# Host.net
KiCad netlist of a schematic drawn in Altium Designer
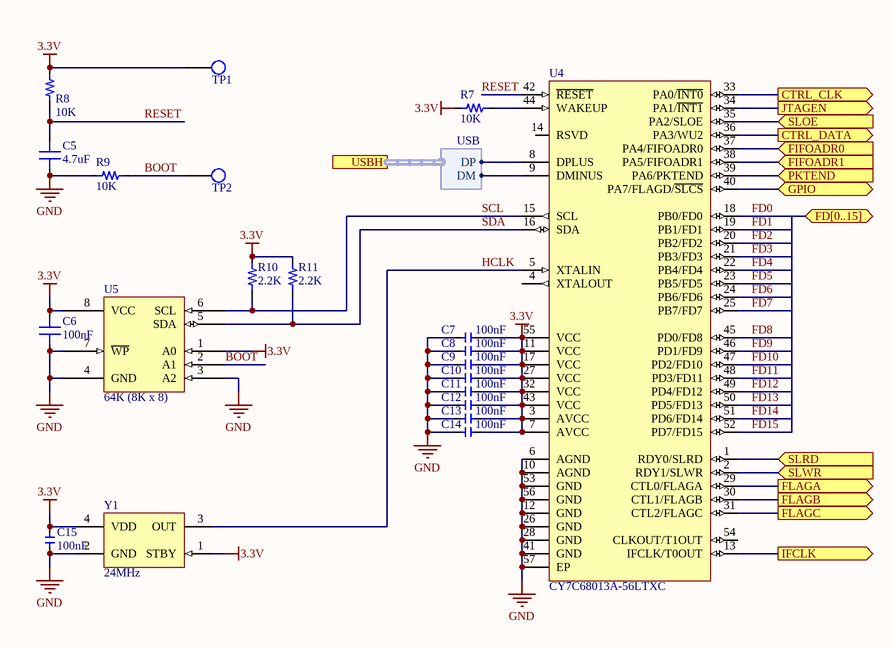
[diagram p0: Host.SchDoc]

(export (version "E")
  (design (tool "Eeschema 10.0.6"))
  (components
    (comp (ref "C5")
      (value "4.7uF")
      (footprint "CAP 0402/1005")
      (description "CAP CER 4.7UF 6.3V X5R 0402")
      (fields (field (name "PART NUMBER") "GRM155R60J475ME87D") (field (name "MANUFACTURER") "Murata"))
      (libsource (lib "") (part "Capacitor_1"))
    )
    (comp (ref "C6")
      (value "100nF")
      (footprint "CAP 0402/1005")
      (description "CAP CER 100NF 25V X5R 0402")
      (fields (field (name "PART NUMBER") "GRM155R61E104KA87D") (field (name "MANUFACTURER") "Murata"))
      (libsource (lib "") (part "Capacitor_1"))
    )
    (comp (ref "C7")
      (value "100nF")
      (footprint "CAP 0402/1005")
      (description "CAP CER 100NF 25V X5R 0402")
      (fields (field (name "PART NUMBER") "GRM155R61E104KA87D") (field (name "MANUFACTURER") "Murata"))
      (libsource (lib "Mengsklib") (part "Capacitor"))
    )
    (comp (ref "C8")
      (value "100nF")
      (footprint "CAP 0402/1005")
      (description "CAP CER 100NF 25V X5R 0402")
      (fields (field (name "PART NUMBER") "GRM155R61E104KA87D") (field (name "MANUFACTURER") "Murata"))
      (libsource (lib "Mengsklib") (part "Capacitor"))
    )
    (comp (ref "C9")
      (value "100nF")
      (footprint "CAP 0402/1005")
      (description "CAP CER 100NF 25V X5R 0402")
      (fields (field (name "PART NUMBER") "GRM155R61E104KA87D") (field (name "MANUFACTURER") "Murata"))
      (libsource (lib "Mengsklib") (part "Capacitor"))
    )
    (comp (ref "C10")
      (value "100nF")
      (footprint "CAP 0402/1005")
      (description "CAP CER 100NF 25V X5R 0402")
      (fields (field (name "PART NUMBER") "GRM155R61E104KA87D") (field (name "MANUFACTURER") "Murata"))
      (libsource (lib "Mengsklib") (part "Capacitor"))
    )
    (comp (ref "C11")
      (value "100nF")
      (footprint "CAP 0402/1005")
      (description "CAP CER 100NF 25V X5R 0402")
      (fields (field (name "PART NUMBER") "GRM155R61E104KA87D") (field (name "MANUFACTURER") "Murata"))
      (libsource (lib "Mengsklib") (part "Capacitor"))
    )
    (comp (ref "C12")
      (value "100nF")
      (footprint "CAP 0402/1005")
      (description "CAP CER 100NF 25V X5R 0402")
      (fields (field (name "PART NUMBER") "GRM155R61E104KA87D") (field (name "MANUFACTURER") "Murata"))
      (libsource (lib "Mengsklib") (part "Capacitor"))
    )
    (comp (ref "C13")
      (value "100nF")
      (footprint "CAP 0402/1005")
      (description "CAP CER 100NF 25V X5R 0402")
      (fields (field (name "PART NUMBER") "GRM155R61E104KA87D") (field (name "MANUFACTURER") "Murata"))
      (libsource (lib "Mengsklib") (part "Capacitor"))
    )
    (comp (ref "C14")
      (value "100nF")
      (footprint "CAP 0402/1005")
      (description "CAP CER 100NF 25V X5R 0402")
      (fields (field (name "PART NUMBER") "GRM155R61E104KA87D") (field (name "MANUFACTURER") "Murata"))
      (libsource (lib "Mengsklib") (part "Capacitor"))
    )
    (comp (ref "C15")
      (value "100nF")
      (footprint "CAP 0402/1005")
      (description "CAP CER 100NF 25V X5R 0402")
      (fields (field (name "PART NUMBER") "GRM155R61E104KA87D") (field (name "MANUFACTURER") "Murata"))
      (libsource (lib "Mengsklib") (part "Capacitor"))
    )
    (comp (ref "R7")
      (value "10K")
      (footprint "RES 0402/1005")
      (description "RES SMD 10K OHM 1% 1/16W 0402")
      (fields (field (name "PART NUMBER") "RC0402FR-0710KL") (field (name "MANUFACTURER") "Yageo"))
      (libsource (lib "Mengsklib") (part "Resistor"))
    )
    (comp (ref "R8")
      (value "10K")
      (footprint "RES 0402/1005")
      (description "RES SMD 10K OHM 1% 1/16W 0402")
      (fields (field (name "PART NUMBER") "RC0402FR-0710KL") (field (name "MANUFACTURER") "Yageo"))
      (libsource (lib "Mengsklib") (part "Resistor"))
    )
    (comp (ref "R9")
      (value "10K")
      (footprint "RES 0402/1005")
      (description "RES SMD 10K OHM 1% 1/16W 0402")
      (fields (field (name "PART NUMBER") "RC0402FR-0710KL") (field (name "MANUFACTURER") "Yageo"))
      (libsource (lib "Mengsklib") (part "Resistor"))
    )
    (comp (ref "R10")
      (value "2.2K")
      (footprint "RES 0402/1005")
      (description "RES SMD 2.2K OHM 1% 1/16W 0402")
      (fields (field (name "PART NUMBER") "RC0402FR-072K2L") (field (name "MANUFACTURER") "Yageo"))
      (libsource (lib "Mengsklib") (part "Resistor"))
    )
    (comp (ref "R11")
      (value "2.2K")
      (footprint "RES 0402/1005")
      (description "RES SMD 2.2K OHM 1% 1/16W 0402")
      (fields (field (name "PART NUMBER") "RC0402FR-072K2L") (field (name "MANUFACTURER") "Yageo"))
      (libsource (lib "Mengsklib") (part "Resistor"))
    )
    (comp (ref "TP1") (value "Test Point") (footprint "TP 1MM") (libsource (lib "Mengsklib") (part "TP")))
    (comp (ref "TP2") (value "Test Point") (footprint "TP 1MM") (libsource (lib "Mengsklib") (part "TP")))
    (comp (ref "U4")
      (value "CY7C68013A-56LTXC")
      (footprint "QFN50P800X800X90_HS-57N")
      (description "MCU USB PHERIPH FX2LP 56VQFN")
      (fields (field (name "MANUFACTURER") "Infineon"))
      (libsource (lib "Mengsklib") (part "CY7C68013A_QFN56"))
    )
    (comp (ref "U5")
      (value "64K (8K x 8)")
      (footprint "MICROCHIP TSSOP-8 ST")
      (description "IC EEPROM 64KBIT 400KHZ 8TSSOP")
      (fields (field (name "PART NUMBER") "24LC64-I/ST") (field (name "MANUFACTURER") "Microchip Technology"))
      (libsource (lib "Mengsklib") (part "EEPROM_I2C_8P"))
    )
    (comp (ref "Y1")
      (value "24MHz")
      (footprint "WE-SPXO_IQXO-540")
      (description "OSC XO 24MHz 3.3V 2016 SMD")
      (fields (field (name "PART NUMBER") "830208215109") (field (name "MANUFACTURER") "Wurth"))
      (libsource (lib "Mengsklib") (part "WE-SPXO_IQXO-540"))
    )
  )
  (nets
    (net (code "2") (name "/BOOT") (class "Default")
      (node (ref "R9") (pin "2") (pinfunction "2_2") (pintype "passive"))
      (node (ref "TP2") (pin "1") (pinfunction "1_1") (pintype "passive"))
      (node (ref "U5") (pin "2") (pinfunction "A1_2") (pintype "input"))
    )
    (net (code "3") (name "/CTRL_CLK") (class "Default")
      (node (ref "U4") (pin "33") (pinfunction "PA0/~{INT0}_33") (pintype "bidirectional"))
    )
    (net (code "4") (name "/CTRL_DATA") (class "Default")
      (node (ref "U4") (pin "36") (pinfunction "PA3/WU2_36") (pintype "bidirectional"))
    )
    (net (code "5") (name "/DM") (class "Default")
      (node (ref "U4") (pin "9") (pinfunction "DMINUS_9") (pintype "passive"))
    )
    (net (code "6") (name "/DP") (class "Default")
      (node (ref "U4") (pin "8") (pinfunction "DPLUS_8") (pintype "passive"))
    )
    (net (code "7") (name "/FD0") (class "Default")
      (node (ref "U4") (pin "18") (pinfunction "PB0/FD0_18") (pintype "bidirectional"))
    )
    (net (code "8") (name "/FD1") (class "Default")
      (node (ref "U4") (pin "19") (pinfunction "PB1/FD1_19") (pintype "bidirectional"))
    )
    (net (code "9") (name "/FD2") (class "Default")
      (node (ref "U4") (pin "20") (pinfunction "PB2/FD2_20") (pintype "bidirectional"))
    )
    (net (code "10") (name "/FD3") (class "Default")
      (node (ref "U4") (pin "21") (pinfunction "PB3/FD3_21") (pintype "bidirectional"))
    )
    (net (code "11") (name "/FD4") (class "Default")
      (node (ref "U4") (pin "22") (pinfunction "PB4/FD4_22") (pintype "bidirectional"))
    )
    (net (code "12") (name "/FD5") (class "Default")
      (node (ref "U4") (pin "23") (pinfunction "PB5/FD5_23") (pintype "bidirectional"))
    )
    (net (code "13") (name "/FD6") (class "Default")
      (node (ref "U4") (pin "24") (pinfunction "PB6/FD6_24") (pintype "bidirectional"))
    )
    (net (code "14") (name "/FD7") (class "Default")
      (node (ref "U4") (pin "25") (pinfunction "PB7/FD7_25") (pintype "bidirectional"))
    )
    (net (code "15") (name "/FD8") (class "Default")
      (node (ref "U4") (pin "45") (pinfunction "PD0/FD8_45") (pintype "bidirectional"))
    )
    (net (code "16") (name "/FD9") (class "Default")
      (node (ref "U4") (pin "46") (pinfunction "PD1/FD9_46") (pintype "bidirectional"))
    )
    (net (code "17") (name "/FD10") (class "Default")
      (node (ref "U4") (pin "47") (pinfunction "PD2/FD10_47") (pintype "bidirectional"))
    )
    (net (code "18") (name "/FD11") (class "Default")
      (node (ref "U4") (pin "48") (pinfunction "PD3/FD11_48") (pintype "bidirectional"))
    )
    (net (code "19") (name "/FD12") (class "Default")
      (node (ref "U4") (pin "49") (pinfunction "PD4/FD12_49") (pintype "bidirectional"))
    )
    (net (code "20") (name "/FD13") (class "Default")
      (node (ref "U4") (pin "50") (pinfunction "PD5/FD13_50") (pintype "bidirectional"))
    )
    (net (code "21") (name "/FD14") (class "Default")
      (node (ref "U4") (pin "51") (pinfunction "PD6/FD14_51") (pintype "bidirectional"))
    )
    (net (code "22") (name "/FD15") (class "Default")
      (node (ref "U4") (pin "52") (pinfunction "PD7/FD15_52") (pintype "bidirectional"))
    )
    (net (code "24") (name "/FIFOADR0") (class "Default")
      (node (ref "U4") (pin "37") (pinfunction "PA4/FIFOADR0_37") (pintype "bidirectional"))
    )
    (net (code "25") (name "/FIFOADR1") (class "Default")
      (node (ref "U4") (pin "38") (pinfunction "PA5/FIFOADR1_38") (pintype "bidirectional"))
    )
    (net (code "26") (name "/FLAGA") (class "Default")
      (node (ref "U4") (pin "29") (pinfunction "CTL0/FLAGA_29") (pintype "bidirectional"))
    )
    (net (code "27") (name "/FLAGB") (class "Default")
      (node (ref "U4") (pin "30") (pinfunction "CTL1/FLAGB_30") (pintype "bidirectional"))
    )
    (net (code "28") (name "/FLAGC") (class "Default")
      (node (ref "U4") (pin "31") (pinfunction "CTL2/FLAGC_31") (pintype "bidirectional"))
    )
    (net (code "29") (name "/GPIO") (class "Default")
      (node (ref "U4") (pin "40") (pinfunction "PA7/FLAGD/~{SLCS}_40") (pintype "bidirectional"))
    )
    (net (code "30") (name "/HCLK") (class "Default")
      (node (ref "U4") (pin "5") (pinfunction "XTALIN_5") (pintype "input"))
      (node (ref "Y1") (pin "3") (pinfunction "OUT_3") (pintype "passive"))
    )
    (net (code "31") (name "/IFCLK") (class "Default")
      (node (ref "U4") (pin "13") (pinfunction "IFCLK/T0OUT_13") (pintype "bidirectional"))
    )
    (net (code "32") (name "/JTAGEN") (class "Default")
      (node (ref "U4") (pin "34") (pinfunction "PA1/~{INT1}_34") (pintype "bidirectional"))
    )
    (net (code "33") (name "/PKTEND") (class "Default")
      (node (ref "U4") (pin "39") (pinfunction "PA6/PKTEND_39") (pintype "bidirectional"))
    )
    (net (code "34") (name "/RESET") (class "Default")
      (node (ref "C5") (pin "1") (pinfunction "1_1") (pintype "passive"))
      (node (ref "R8") (pin "1") (pinfunction "1_1") (pintype "passive"))
      (node (ref "U4") (pin "42") (pinfunction "~{RESET}_42") (pintype "input"))
    )
    (net (code "35") (name "/SCL") (class "Default")
      (node (ref "R10") (pin "1") (pinfunction "1_1") (pintype "passive"))
      (node (ref "U4") (pin "15") (pinfunction "SCL_15") (pintype "output"))
      (node (ref "U5") (pin "6") (pinfunction "SCL_6") (pintype "input"))
    )
    (net (code "36") (name "/SDA") (class "Default")
      (node (ref "R11") (pin "1") (pinfunction "1_1") (pintype "passive"))
      (node (ref "U4") (pin "16") (pinfunction "SDA_16") (pintype "bidirectional"))
      (node (ref "U5") (pin "5") (pinfunction "SDA_5") (pintype "bidirectional"))
    )
    (net (code "37") (name "/SLOE") (class "Default")
      (node (ref "U4") (pin "35") (pinfunction "PA2/SLOE_35") (pintype "bidirectional"))
    )
    (net (code "38") (name "/SLRD") (class "Default")
      (node (ref "U4") (pin "1") (pinfunction "RDY0/SLRD_1") (pintype "bidirectional"))
    )
    (net (code "39") (name "/SLWR") (class "Default")
      (node (ref "U4") (pin "2") (pinfunction "RDY1/SLWR_2") (pintype "bidirectional"))
    )
    (net (code "41") (name "3.3V") (class "Default")
      (node (ref "C10") (pin "2") (pinfunction "2_2") (pintype "passive"))
      (node (ref "C11") (pin "2") (pinfunction "2_2") (pintype "passive"))
      (node (ref "C12") (pin "2") (pinfunction "2_2") (pintype "passive"))
      (node (ref "C13") (pin "2") (pinfunction "2_2") (pintype "passive"))
      (node (ref "C14") (pin "2") (pinfunction "2_2") (pintype "passive"))
      (node (ref "C15") (pin "1") (pinfunction "1_1") (pintype "passive"))
      (node (ref "C6") (pin "1") (pinfunction "1_1") (pintype "passive"))
      (node (ref "C7") (pin "1") (pinfunction "1_1") (pintype "passive"))
      (node (ref "C8") (pin "2") (pinfunction "2_2") (pintype "passive"))
      (node (ref "C9") (pin "2") (pinfunction "2_2") (pintype "passive"))
      (node (ref "R10") (pin "2") (pinfunction "2_2") (pintype "passive"))
      (node (ref "R11") (pin "2") (pinfunction "2_2") (pintype "passive"))
      (node (ref "R7") (pin "2") (pinfunction "2_2") (pintype "passive"))
      (node (ref "R8") (pin "2") (pinfunction "2_2") (pintype "passive"))
      (node (ref "TP1") (pin "1") (pinfunction "1_1") (pintype "passive"))
      (node (ref "U4") (pin "11") (pinfunction "VCC_11") (pintype "passive"))
      (node (ref "U4") (pin "17") (pinfunction "VCC_17") (pintype "passive"))
      (node (ref "U4") (pin "27") (pinfunction "VCC_27") (pintype "passive"))
      (node (ref "U4") (pin "3") (pinfunction "AVCC_3") (pintype "passive"))
      (node (ref "U4") (pin "32") (pinfunction "VCC_32") (pintype "passive"))
      (node (ref "U4") (pin "43") (pinfunction "VCC_43") (pintype "passive"))
      (node (ref "U4") (pin "55") (pinfunction "VCC_55") (pintype "passive"))
      (node (ref "U4") (pin "7") (pinfunction "AVCC_7") (pintype "passive"))
      (node (ref "U5") (pin "1") (pinfunction "A0_1") (pintype "input"))
      (node (ref "U5") (pin "8") (pinfunction "VCC_8") (pintype "power_in"))
      (node (ref "Y1") (pin "1") (pinfunction "STBY_1") (pintype "input"))
      (node (ref "Y1") (pin "4") (pinfunction "VDD_4") (pintype "passive"))
    )
    (net (code "42") (name "GND") (class "Default")
      (node (ref "C10") (pin "1") (pinfunction "1_1") (pintype "passive"))
      (node (ref "C11") (pin "1") (pinfunction "1_1") (pintype "passive"))
      (node (ref "C12") (pin "1") (pinfunction "1_1") (pintype "passive"))
      (node (ref "C13") (pin "1") (pinfunction "1_1") (pintype "passive"))
      (node (ref "C14") (pin "1") (pinfunction "1_1") (pintype "passive"))
      (node (ref "C15") (pin "2") (pinfunction "2_2") (pintype "passive"))
      (node (ref "C5") (pin "2") (pinfunction "2_2") (pintype "passive"))
      (node (ref "C6") (pin "2") (pinfunction "2_2") (pintype "passive"))
      (node (ref "C7") (pin "2") (pinfunction "2_2") (pintype "passive"))
      (node (ref "C8") (pin "1") (pinfunction "1_1") (pintype "passive"))
      (node (ref "C9") (pin "1") (pinfunction "1_1") (pintype "passive"))
      (node (ref "R9") (pin "1") (pinfunction "1_1") (pintype "passive"))
      (node (ref "U4") (pin "10") (pinfunction "AGND_10") (pintype "passive"))
      (node (ref "U4") (pin "12") (pinfunction "GND_12") (pintype "passive"))
      (node (ref "U4") (pin "26") (pinfunction "GND_26") (pintype "passive"))
      (node (ref "U4") (pin "28") (pinfunction "GND_28") (pintype "passive"))
      (node (ref "U4") (pin "41") (pinfunction "GND_41") (pintype "passive"))
      (node (ref "U4") (pin "53") (pinfunction "GND_53") (pintype "passive"))
      (node (ref "U4") (pin "56") (pinfunction "GND_56") (pintype "passive"))
      (node (ref "U4") (pin "57") (pinfunction "EP_57") (pintype "passive"))
      (node (ref "U4") (pin "6") (pinfunction "AGND_6") (pintype "passive"))
      (node (ref "U5") (pin "3") (pinfunction "A2_3") (pintype "input"))
      (node (ref "U5") (pin "4") (pinfunction "GND_4") (pintype "power_in"))
      (node (ref "U5") (pin "7") (pinfunction "~{WP}_7") (pintype "input"))
      (node (ref "Y1") (pin "2") (pinfunction "GND_2") (pintype "passive"))
    )
    (net (code "43") (name "Net-(U4-WAKEUP)") (class "Default")
      (node (ref "R7") (pin "1") (pinfunction "1_1") (pintype "passive"))
      (node (ref "U4") (pin "44") (pinfunction "WAKEUP_44") (pintype "input"))
    )
    (net (code "44") (name "unconnected-(U4-CLKOUT{slash}T1OUT-Pad54)") (class "Default")
      (node (ref "U4") (pin "54") (pinfunction "CLKOUT/T1OUT_54") (pintype "bidirectional"))
    )
    (net (code "45") (name "unconnected-(U4-RSVD-Pad14)") (class "Default")
      (node (ref "U4") (pin "14") (pinfunction "RSVD_14") (pintype "passive"))
    )
    (net (code "46") (name "unconnected-(U4-XTALOUT-Pad4)") (class "Default")
      (node (ref "U4") (pin "4") (pinfunction "XTALOUT_4") (pintype "output"))
    )
  )
)
